# S7CAS-PLEIADES-CARTE-MERE_P01_FPGA-BANK1.net
KiCad netlist of a schematic drawn in Altium Designer
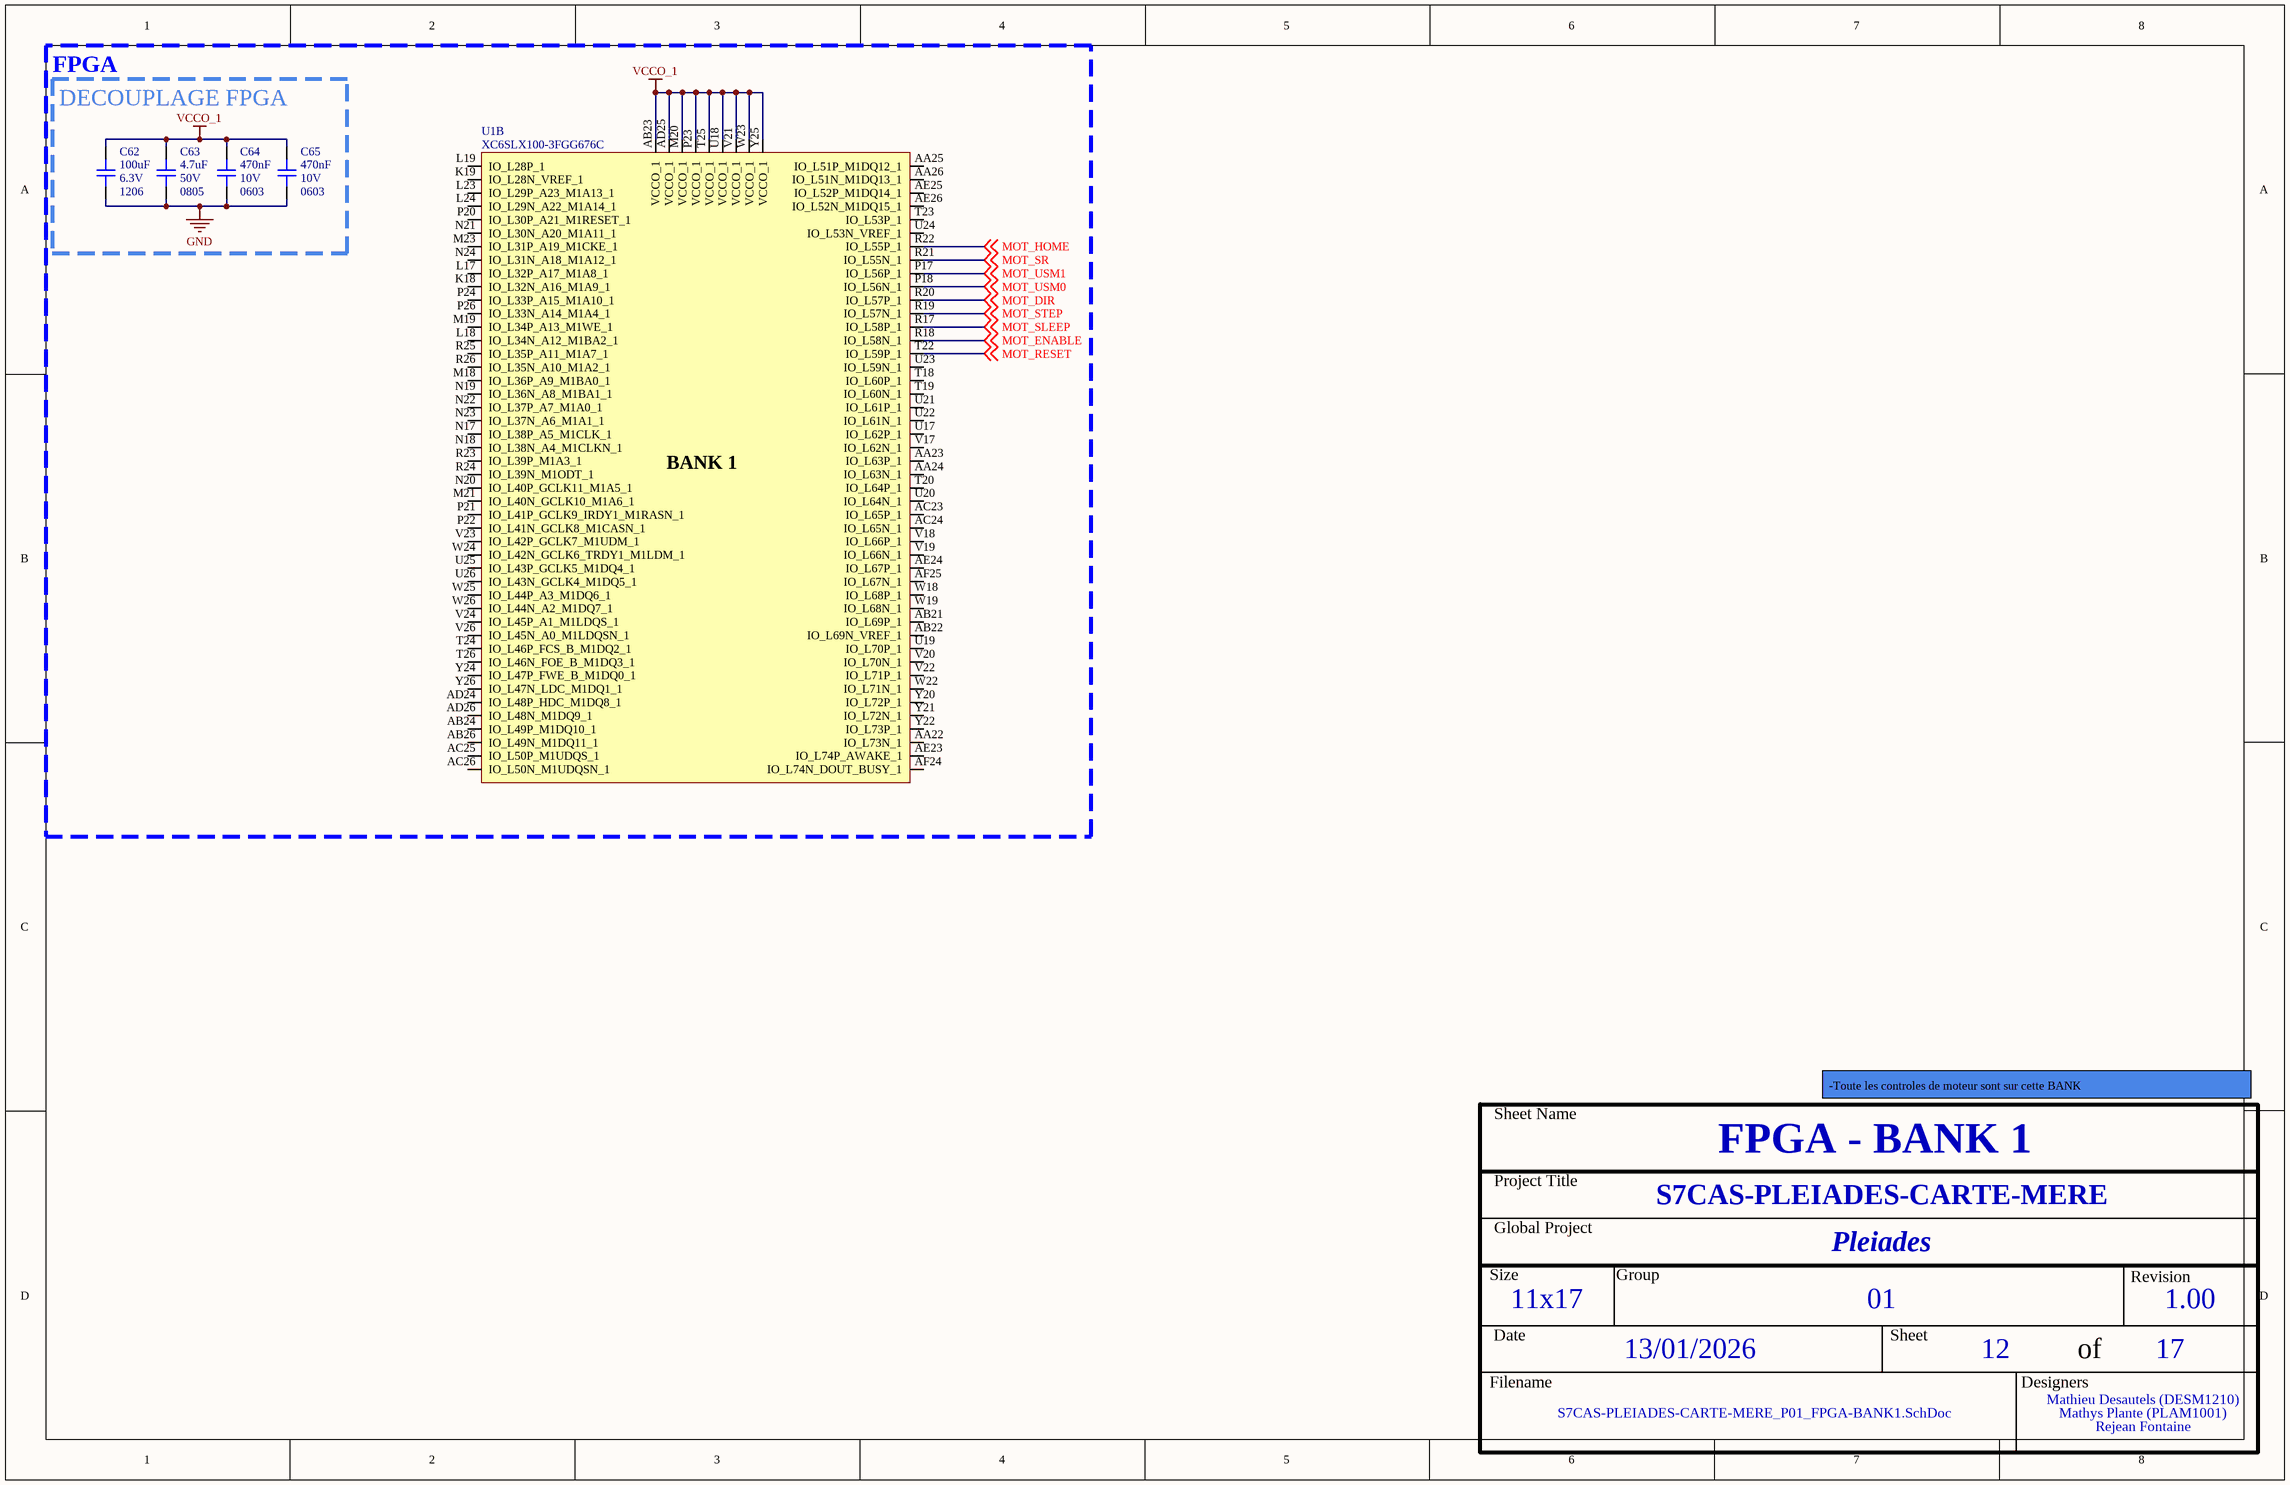
[diagram p0: S7CAS-PLEIADES-CARTE-MERE_P01_FPGA-BANK1.SchDoc]

(export (version "E")
  (design (tool "Eeschema 10.0.6"))
  (components
    (comp (ref "C62")
      (value "100uF")
      (footprint "CAP_1206")
      (description "100 µF ±20% 6.3V Ceramic Capacitor X6T 1206 (3216 Metric)")
      (fields
        (field (name "MFG") "Murata Electronics")
        (field (name "MFG PART NUMBER") "GRM31CD80J107MEA8K")
        (field (name "VOLTAGE") "6.3V")
        (field (name "PACKAGE") "1206")
        (field (name "CREATEDBY") "Jonathan Bouchard")
      )
      (libsource (lib "s7cas_lib2023") (part "CAP - 1206"))
    )
    (comp (ref "C63")
      (value "4.7uF")
      (footprint "CAP_0805")
      (description "4.7 µF ±10% 50V Ceramic Capacitor X5R 0805 (2012 Metric)")
      (fields
        (field (name "MFG") "Murata Electronics")
        (field (name "MFG PART NUMBER") "GRT21BR61H475KE13L")
        (field (name "VOLTAGE") "50V")
        (field (name "PACKAGE") "0805")
        (field (name "CREATEDBY") "Jonathan Bouchard")
      )
      (libsource (lib "s7cas_lib2023") (part "CAP - 0805"))
    )
    (comp (ref "C64")
      (value "470nF")
      (footprint "CAP_0603")
      (description "CAP - 0603")
      (fields
        (field (name "MFG PART NUMBER") "C0603X474K8RAC")
        (field (name "VOLTAGE") "10V")
        (field (name "PACKAGE") "0603")
        (field (name "CREATEDBY") "Jonathan Bouchard")
      )
      (libsource (lib "s7cas_lib2023") (part "CAP - 0603"))
    )
    (comp (ref "C65")
      (value "470nF")
      (footprint "CAP_0603")
      (description "CAP - 0603")
      (fields
        (field (name "MFG PART NUMBER") "C0603X474K8RAC")
        (field (name "VOLTAGE") "10V")
        (field (name "PACKAGE") "0603")
        (field (name "CREATEDBY") "Jonathan Bouchard")
      )
      (libsource (lib "s7cas_lib2023") (part "CAP - 0603"))
    )
    (comp (ref "U1")
      (value "XC6SLX100-3FGG676C")
      (footprint "FPGA_XILINX_FGG676")
      (description "FPGA - XILINX SPARTAN 6 480 I/O - BGA-676")
      (fields
        (field (name "VOLTAGE") "1.14 V ~ 1.26 V")
        (field (name "MFG") "Xilinx")
        (field (name "CREATEDBY") "Jonathan Bouchard")
      )
      (libsource (lib "s7cas_lib2023") (part "FPGA_XC6SLX100-3FGG676C"))
    )
  )
  (nets
    (net (code "1") (name "GND") (class "Default")
      (node (ref "C62") (pin "1") (pinfunction "1_1") (pintype "passive"))
      (node (ref "C63") (pin "1") (pinfunction "1_1") (pintype "passive"))
      (node (ref "C64") (pin "1") (pinfunction "1_1") (pintype "passive"))
      (node (ref "C65") (pin "1") (pinfunction "1_1") (pintype "passive"))
    )
    (net (code "2") (name "MOT_DIR") (class "Default")
      (node (ref "U1") (pin "R20") (pinfunction "IO_L57P_1_R20") (pintype "passive"))
    )
    (net (code "3") (name "MOT_ENABLE") (class "Default")
      (node (ref "U1") (pin "R18") (pinfunction "IO_L58N_1_R18") (pintype "passive"))
    )
    (net (code "4") (name "MOT_HOME") (class "Default")
      (node (ref "U1") (pin "R22") (pinfunction "IO_L55P_1_R22") (pintype "passive"))
    )
    (net (code "5") (name "MOT_RESET") (class "Default")
      (node (ref "U1") (pin "T22") (pinfunction "IO_L59P_1_T22") (pintype "passive"))
    )
    (net (code "6") (name "MOT_SLEEP") (class "Default")
      (node (ref "U1") (pin "R17") (pinfunction "IO_L58P_1_R17") (pintype "passive"))
    )
    (net (code "7") (name "MOT_SR") (class "Default")
      (node (ref "U1") (pin "R21") (pinfunction "IO_L55N_1_R21") (pintype "passive"))
    )
    (net (code "8") (name "MOT_STEP") (class "Default")
      (node (ref "U1") (pin "R19") (pinfunction "IO_L57N_1_R19") (pintype "passive"))
    )
    (net (code "9") (name "MOT_USM0") (class "Default")
      (node (ref "U1") (pin "P18") (pinfunction "IO_L56N_1_P18") (pintype "passive"))
    )
    (net (code "10") (name "MOT_USM1") (class "Default")
      (node (ref "U1") (pin "P17") (pinfunction "IO_L56P_1_P17") (pintype "passive"))
    )
    (net (code "11") (name "VCCO_1") (class "Default")
      (node (ref "C62") (pin "2") (pinfunction "2_2") (pintype "passive"))
      (node (ref "C63") (pin "2") (pinfunction "2_2") (pintype "passive"))
      (node (ref "C64") (pin "2") (pinfunction "2_2") (pintype "passive"))
      (node (ref "C65") (pin "2") (pinfunction "2_2") (pintype "passive"))
      (node (ref "U1") (pin "AB23") (pinfunction "VCCO_1_AB23") (pintype "passive"))
      (node (ref "U1") (pin "AD25") (pinfunction "VCCO_1_AD25") (pintype "passive"))
      (node (ref "U1") (pin "M20") (pinfunction "VCCO_1_M20") (pintype "passive"))
      (node (ref "U1") (pin "P23") (pinfunction "VCCO_1_P23") (pintype "passive"))
      (node (ref "U1") (pin "T25") (pinfunction "VCCO_1_T25") (pintype "passive"))
      (node (ref "U1") (pin "U18") (pinfunction "VCCO_1_U18") (pintype "passive"))
      (node (ref "U1") (pin "V21") (pinfunction "VCCO_1_V21") (pintype "passive"))
      (node (ref "U1") (pin "W23") (pinfunction "VCCO_1_W23") (pintype "passive"))
      (node (ref "U1") (pin "Y25") (pinfunction "VCCO_1_Y25") (pintype "passive"))
    )
    (net (code "12") (name "unconnected-(U1B-IO_L28N_VREF_1-PadK19)") (class "Default")
      (node (ref "U1") (pin "K19") (pinfunction "IO_L28N_VREF_1_K19") (pintype "passive"))
    )
    (net (code "13") (name "unconnected-(U1B-IO_L28P_1-PadL19)") (class "Default")
      (node (ref "U1") (pin "L19") (pinfunction "IO_L28P_1_L19") (pintype "passive"))
    )
    (net (code "14") (name "unconnected-(U1B-IO_L29N_A22_M1A14_1-PadL24)") (class "Default")
      (node (ref "U1") (pin "L24") (pinfunction "IO_L29N_A22_M1A14_1_L24") (pintype "passive"))
    )
    (net (code "15") (name "unconnected-(U1B-IO_L29P_A23_M1A13_1-PadL23)") (class "Default")
      (node (ref "U1") (pin "L23") (pinfunction "IO_L29P_A23_M1A13_1_L23") (pintype "passive"))
    )
    (net (code "16") (name "unconnected-(U1B-IO_L30N_A20_M1A11_1-PadN21)") (class "Default")
      (node (ref "U1") (pin "N21") (pinfunction "IO_L30N_A20_M1A11_1_N21") (pintype "passive"))
    )
    (net (code "17") (name "unconnected-(U1B-IO_L30P_A21_M1RESET_1-PadP20)") (class "Default")
      (node (ref "U1") (pin "P20") (pinfunction "IO_L30P_A21_M1RESET_1_P20") (pintype "passive"))
    )
    (net (code "18") (name "unconnected-(U1B-IO_L31N_A18_M1A12_1-PadN24)") (class "Default")
      (node (ref "U1") (pin "N24") (pinfunction "IO_L31N_A18_M1A12_1_N24") (pintype "passive"))
    )
    (net (code "19") (name "unconnected-(U1B-IO_L31P_A19_M1CKE_1-PadM23)") (class "Default")
      (node (ref "U1") (pin "M23") (pinfunction "IO_L31P_A19_M1CKE_1_M23") (pintype "passive"))
    )
    (net (code "20") (name "unconnected-(U1B-IO_L32N_A16_M1A9_1-PadK18)") (class "Default")
      (node (ref "U1") (pin "K18") (pinfunction "IO_L32N_A16_M1A9_1_K18") (pintype "passive"))
    )
    (net (code "21") (name "unconnected-(U1B-IO_L32P_A17_M1A8_1-PadL17)") (class "Default")
      (node (ref "U1") (pin "L17") (pinfunction "IO_L32P_A17_M1A8_1_L17") (pintype "passive"))
    )
    (net (code "22") (name "unconnected-(U1B-IO_L33N_A14_M1A4_1-PadP26)") (class "Default")
      (node (ref "U1") (pin "P26") (pinfunction "IO_L33N_A14_M1A4_1_P26") (pintype "passive"))
    )
    (net (code "23") (name "unconnected-(U1B-IO_L33P_A15_M1A10_1-PadP24)") (class "Default")
      (node (ref "U1") (pin "P24") (pinfunction "IO_L33P_A15_M1A10_1_P24") (pintype "passive"))
    )
    (net (code "24") (name "unconnected-(U1B-IO_L34N_A12_M1BA2_1-PadL18)") (class "Default")
      (node (ref "U1") (pin "L18") (pinfunction "IO_L34N_A12_M1BA2_1_L18") (pintype "passive"))
    )
    (net (code "25") (name "unconnected-(U1B-IO_L34P_A13_M1WE_1-PadM19)") (class "Default")
      (node (ref "U1") (pin "M19") (pinfunction "IO_L34P_A13_M1WE_1_M19") (pintype "passive"))
    )
    (net (code "26") (name "unconnected-(U1B-IO_L35N_A10_M1A2_1-PadR26)") (class "Default")
      (node (ref "U1") (pin "R26") (pinfunction "IO_L35N_A10_M1A2_1_R26") (pintype "passive"))
    )
    (net (code "27") (name "unconnected-(U1B-IO_L35P_A11_M1A7_1-PadR25)") (class "Default")
      (node (ref "U1") (pin "R25") (pinfunction "IO_L35P_A11_M1A7_1_R25") (pintype "passive"))
    )
    (net (code "28") (name "unconnected-(U1B-IO_L36N_A8_M1BA1_1-PadN19)") (class "Default")
      (node (ref "U1") (pin "N19") (pinfunction "IO_L36N_A8_M1BA1_1_N19") (pintype "passive"))
    )
    (net (code "29") (name "unconnected-(U1B-IO_L36P_A9_M1BA0_1-PadM18)") (class "Default")
      (node (ref "U1") (pin "M18") (pinfunction "IO_L36P_A9_M1BA0_1_M18") (pintype "passive"))
    )
    (net (code "30") (name "unconnected-(U1B-IO_L37N_A6_M1A1_1-PadN23)") (class "Default")
      (node (ref "U1") (pin "N23") (pinfunction "IO_L37N_A6_M1A1_1_N23") (pintype "passive"))
    )
    (net (code "31") (name "unconnected-(U1B-IO_L37P_A7_M1A0_1-PadN22)") (class "Default")
      (node (ref "U1") (pin "N22") (pinfunction "IO_L37P_A7_M1A0_1_N22") (pintype "passive"))
    )
    (net (code "32") (name "unconnected-(U1B-IO_L38N_A4_M1CLKN_1-PadN18)") (class "Default")
      (node (ref "U1") (pin "N18") (pinfunction "IO_L38N_A4_M1CLKN_1_N18") (pintype "passive"))
    )
    (net (code "33") (name "unconnected-(U1B-IO_L38P_A5_M1CLK_1-PadN17)") (class "Default")
      (node (ref "U1") (pin "N17") (pinfunction "IO_L38P_A5_M1CLK_1_N17") (pintype "passive"))
    )
    (net (code "34") (name "unconnected-(U1B-IO_L39N_M1ODT_1-PadR24)") (class "Default")
      (node (ref "U1") (pin "R24") (pinfunction "IO_L39N_M1ODT_1_R24") (pintype "passive"))
    )
    (net (code "35") (name "unconnected-(U1B-IO_L39P_M1A3_1-PadR23)") (class "Default")
      (node (ref "U1") (pin "R23") (pinfunction "IO_L39P_M1A3_1_R23") (pintype "passive"))
    )
    (net (code "36") (name "unconnected-(U1B-IO_L40N_GCLK10_M1A6_1-PadM21)") (class "Default")
      (node (ref "U1") (pin "M21") (pinfunction "IO_L40N_GCLK10_M1A6_1_M21") (pintype "passive"))
    )
    (net (code "37") (name "unconnected-(U1B-IO_L40P_GCLK11_M1A5_1-PadN20)") (class "Default")
      (node (ref "U1") (pin "N20") (pinfunction "IO_L40P_GCLK11_M1A5_1_N20") (pintype "passive"))
    )
    (net (code "38") (name "unconnected-(U1B-IO_L41N_GCLK8_M1CASN_1-PadP22)") (class "Default")
      (node (ref "U1") (pin "P22") (pinfunction "IO_L41N_GCLK8_M1CASN_1_P22") (pintype "passive"))
    )
    (net (code "39") (name "unconnected-(U1B-IO_L41P_GCLK9_IRDY1_M1RASN_1-PadP21)") (class "Default")
      (node (ref "U1") (pin "P21") (pinfunction "IO_L41P_GCLK9_IRDY1_M1RASN_1_P21") (pintype "passive"))
    )
    (net (code "40") (name "unconnected-(U1B-IO_L42N_GCLK6_TRDY1_M1LDM_1-PadW24)") (class "Default")
      (node (ref "U1") (pin "W24") (pinfunction "IO_L42N_GCLK6_TRDY1_M1LDM_1_W24") (pintype "passive"))
    )
    (net (code "41") (name "unconnected-(U1B-IO_L42P_GCLK7_M1UDM_1-PadV23)") (class "Default")
      (node (ref "U1") (pin "V23") (pinfunction "IO_L42P_GCLK7_M1UDM_1_V23") (pintype "passive"))
    )
    (net (code "42") (name "unconnected-(U1B-IO_L43N_GCLK4_M1DQ5_1-PadU26)") (class "Default")
      (node (ref "U1") (pin "U26") (pinfunction "IO_L43N_GCLK4_M1DQ5_1_U26") (pintype "passive"))
    )
    (net (code "43") (name "unconnected-(U1B-IO_L43P_GCLK5_M1DQ4_1-PadU25)") (class "Default")
      (node (ref "U1") (pin "U25") (pinfunction "IO_L43P_GCLK5_M1DQ4_1_U25") (pintype "passive"))
    )
    (net (code "44") (name "unconnected-(U1B-IO_L44N_A2_M1DQ7_1-PadW26)") (class "Default")
      (node (ref "U1") (pin "W26") (pinfunction "IO_L44N_A2_M1DQ7_1_W26") (pintype "passive"))
    )
    (net (code "45") (name "unconnected-(U1B-IO_L44P_A3_M1DQ6_1-PadW25)") (class "Default")
      (node (ref "U1") (pin "W25") (pinfunction "IO_L44P_A3_M1DQ6_1_W25") (pintype "passive"))
    )
    (net (code "46") (name "unconnected-(U1B-IO_L45N_A0_M1LDQSN_1-PadV26)") (class "Default")
      (node (ref "U1") (pin "V26") (pinfunction "IO_L45N_A0_M1LDQSN_1_V26") (pintype "passive"))
    )
    (net (code "47") (name "unconnected-(U1B-IO_L45P_A1_M1LDQS_1-PadV24)") (class "Default")
      (node (ref "U1") (pin "V24") (pinfunction "IO_L45P_A1_M1LDQS_1_V24") (pintype "passive"))
    )
    (net (code "48") (name "unconnected-(U1B-IO_L46N_FOE_B_M1DQ3_1-PadT26)") (class "Default")
      (node (ref "U1") (pin "T26") (pinfunction "IO_L46N_FOE_B_M1DQ3_1_T26") (pintype "passive"))
    )
    (net (code "49") (name "unconnected-(U1B-IO_L46P_FCS_B_M1DQ2_1-PadT24)") (class "Default")
      (node (ref "U1") (pin "T24") (pinfunction "IO_L46P_FCS_B_M1DQ2_1_T24") (pintype "passive"))
    )
    (net (code "50") (name "unconnected-(U1B-IO_L47N_LDC_M1DQ1_1-PadY26)") (class "Default")
      (node (ref "U1") (pin "Y26") (pinfunction "IO_L47N_LDC_M1DQ1_1_Y26") (pintype "passive"))
    )
    (net (code "51") (name "unconnected-(U1B-IO_L47P_FWE_B_M1DQ0_1-PadY24)") (class "Default")
      (node (ref "U1") (pin "Y24") (pinfunction "IO_L47P_FWE_B_M1DQ0_1_Y24") (pintype "passive"))
    )
    (net (code "52") (name "unconnected-(U1B-IO_L48N_M1DQ9_1-PadAD26)") (class "Default")
      (node (ref "U1") (pin "AD26") (pinfunction "IO_L48N_M1DQ9_1_AD26") (pintype "passive"))
    )
    (net (code "53") (name "unconnected-(U1B-IO_L48P_HDC_M1DQ8_1-PadAD24)") (class "Default")
      (node (ref "U1") (pin "AD24") (pinfunction "IO_L48P_HDC_M1DQ8_1_AD24") (pintype "passive"))
    )
    (net (code "54") (name "unconnected-(U1B-IO_L49N_M1DQ11_1-PadAB26)") (class "Default")
      (node (ref "U1") (pin "AB26") (pinfunction "IO_L49N_M1DQ11_1_AB26") (pintype "passive"))
    )
    (net (code "55") (name "unconnected-(U1B-IO_L49P_M1DQ10_1-PadAB24)") (class "Default")
      (node (ref "U1") (pin "AB24") (pinfunction "IO_L49P_M1DQ10_1_AB24") (pintype "passive"))
    )
    (net (code "56") (name "unconnected-(U1B-IO_L50N_M1UDQSN_1-PadAC26)") (class "Default")
      (node (ref "U1") (pin "AC26") (pinfunction "IO_L50N_M1UDQSN_1_AC26") (pintype "passive"))
    )
    (net (code "57") (name "unconnected-(U1B-IO_L50P_M1UDQS_1-PadAC25)") (class "Default")
      (node (ref "U1") (pin "AC25") (pinfunction "IO_L50P_M1UDQS_1_AC25") (pintype "passive"))
    )
    (net (code "58") (name "unconnected-(U1B-IO_L51N_M1DQ13_1-PadAA26)") (class "Default")
      (node (ref "U1") (pin "AA26") (pinfunction "IO_L51N_M1DQ13_1_AA26") (pintype "passive"))
    )
    (net (code "59") (name "unconnected-(U1B-IO_L51P_M1DQ12_1-PadAA25)") (class "Default")
      (node (ref "U1") (pin "AA25") (pinfunction "IO_L51P_M1DQ12_1_AA25") (pintype "passive"))
    )
    (net (code "60") (name "unconnected-(U1B-IO_L52N_M1DQ15_1-PadAE26)") (class "Default")
      (node (ref "U1") (pin "AE26") (pinfunction "IO_L52N_M1DQ15_1_AE26") (pintype "passive"))
    )
    (net (code "61") (name "unconnected-(U1B-IO_L52P_M1DQ14_1-PadAE25)") (class "Default")
      (node (ref "U1") (pin "AE25") (pinfunction "IO_L52P_M1DQ14_1_AE25") (pintype "passive"))
    )
    (net (code "62") (name "unconnected-(U1B-IO_L53N_VREF_1-PadU24)") (class "Default")
      (node (ref "U1") (pin "U24") (pinfunction "IO_L53N_VREF_1_U24") (pintype "passive"))
    )
    (net (code "63") (name "unconnected-(U1B-IO_L53P_1-PadT23)") (class "Default")
      (node (ref "U1") (pin "T23") (pinfunction "IO_L53P_1_T23") (pintype "passive"))
    )
    (net (code "64") (name "unconnected-(U1B-IO_L59N_1-PadU23)") (class "Default")
      (node (ref "U1") (pin "U23") (pinfunction "IO_L59N_1_U23") (pintype "passive"))
    )
    (net (code "65") (name "unconnected-(U1B-IO_L60N_1-PadT19)") (class "Default")
      (node (ref "U1") (pin "T19") (pinfunction "IO_L60N_1_T19") (pintype "passive"))
    )
    (net (code "66") (name "unconnected-(U1B-IO_L60P_1-PadT18)") (class "Default")
      (node (ref "U1") (pin "T18") (pinfunction "IO_L60P_1_T18") (pintype "passive"))
    )
    (net (code "67") (name "unconnected-(U1B-IO_L61N_1-PadU22)") (class "Default")
      (node (ref "U1") (pin "U22") (pinfunction "IO_L61N_1_U22") (pintype "passive"))
    )
    (net (code "68") (name "unconnected-(U1B-IO_L61P_1-PadU21)") (class "Default")
      (node (ref "U1") (pin "U21") (pinfunction "IO_L61P_1_U21") (pintype "passive"))
    )
    (net (code "69") (name "unconnected-(U1B-IO_L62N_1-PadV17)") (class "Default")
      (node (ref "U1") (pin "V17") (pinfunction "IO_L62N_1_V17") (pintype "passive"))
    )
    (net (code "70") (name "unconnected-(U1B-IO_L62P_1-PadU17)") (class "Default")
      (node (ref "U1") (pin "U17") (pinfunction "IO_L62P_1_U17") (pintype "passive"))
    )
    (net (code "71") (name "unconnected-(U1B-IO_L63N_1-PadAA24)") (class "Default")
      (node (ref "U1") (pin "AA24") (pinfunction "IO_L63N_1_AA24") (pintype "passive"))
    )
    (net (code "72") (name "unconnected-(U1B-IO_L63P_1-PadAA23)") (class "Default")
      (node (ref "U1") (pin "AA23") (pinfunction "IO_L63P_1_AA23") (pintype "passive"))
    )
    (net (code "73") (name "unconnected-(U1B-IO_L64N_1-PadU20)") (class "Default")
      (node (ref "U1") (pin "U20") (pinfunction "IO_L64N_1_U20") (pintype "passive"))
    )
    (net (code "74") (name "unconnected-(U1B-IO_L64P_1-PadT20)") (class "Default")
      (node (ref "U1") (pin "T20") (pinfunction "IO_L64P_1_T20") (pintype "passive"))
    )
    (net (code "75") (name "unconnected-(U1B-IO_L65N_1-PadAC24)") (class "Default")
      (node (ref "U1") (pin "AC24") (pinfunction "IO_L65N_1_AC24") (pintype "passive"))
    )
    (net (code "76") (name "unconnected-(U1B-IO_L65P_1-PadAC23)") (class "Default")
      (node (ref "U1") (pin "AC23") (pinfunction "IO_L65P_1_AC23") (pintype "passive"))
    )
    (net (code "77") (name "unconnected-(U1B-IO_L66N_1-PadV19)") (class "Default")
      (node (ref "U1") (pin "V19") (pinfunction "IO_L66N_1_V19") (pintype "passive"))
    )
    (net (code "78") (name "unconnected-(U1B-IO_L66P_1-PadV18)") (class "Default")
      (node (ref "U1") (pin "V18") (pinfunction "IO_L66P_1_V18") (pintype "passive"))
    )
    (net (code "79") (name "unconnected-(U1B-IO_L67N_1-PadAF25)") (class "Default")
      (node (ref "U1") (pin "AF25") (pinfunction "IO_L67N_1_AF25") (pintype "passive"))
    )
    (net (code "80") (name "unconnected-(U1B-IO_L67P_1-PadAE24)") (class "Default")
      (node (ref "U1") (pin "AE24") (pinfunction "IO_L67P_1_AE24") (pintype "passive"))
    )
    (net (code "81") (name "unconnected-(U1B-IO_L68N_1-PadW19)") (class "Default")
      (node (ref "U1") (pin "W19") (pinfunction "IO_L68N_1_W19") (pintype "passive"))
    )
    (net (code "82") (name "unconnected-(U1B-IO_L68P_1-PadW18)") (class "Default")
      (node (ref "U1") (pin "W18") (pinfunction "IO_L68P_1_W18") (pintype "passive"))
    )
    (net (code "83") (name "unconnected-(U1B-IO_L69N_VREF_1-PadAB22)") (class "Default")
      (node (ref "U1") (pin "AB22") (pinfunction "IO_L69N_VREF_1_AB22") (pintype "passive"))
    )
    (net (code "84") (name "unconnected-(U1B-IO_L69P_1-PadAB21)") (class "Default")
      (node (ref "U1") (pin "AB21") (pinfunction "IO_L69P_1_AB21") (pintype "passive"))
    )
    (net (code "85") (name "unconnected-(U1B-IO_L70N_1-PadV20)") (class "Default")
      (node (ref "U1") (pin "V20") (pinfunction "IO_L70N_1_V20") (pintype "passive"))
    )
    (net (code "86") (name "unconnected-(U1B-IO_L70P_1-PadU19)") (class "Default")
      (node (ref "U1") (pin "U19") (pinfunction "IO_L70P_1_U19") (pintype "passive"))
    )
    (net (code "87") (name "unconnected-(U1B-IO_L71N_1-PadW22)") (class "Default")
      (node (ref "U1") (pin "W22") (pinfunction "IO_L71N_1_W22") (pintype "passive"))
    )
    (net (code "88") (name "unconnected-(U1B-IO_L71P_1-PadV22)") (class "Default")
      (node (ref "U1") (pin "V22") (pinfunction "IO_L71P_1_V22") (pintype "passive"))
    )
    (net (code "89") (name "unconnected-(U1B-IO_L72N_1-PadY21)") (class "Default")
      (node (ref "U1") (pin "Y21") (pinfunction "IO_L72N_1_Y21") (pintype "passive"))
    )
    (net (code "90") (name "unconnected-(U1B-IO_L72P_1-PadY20)") (class "Default")
      (node (ref "U1") (pin "Y20") (pinfunction "IO_L72P_1_Y20") (pintype "passive"))
    )
    (net (code "91") (name "unconnected-(U1B-IO_L73N_1-PadAA22)") (class "Default")
      (node (ref "U1") (pin "AA22") (pinfunction "IO_L73N_1_AA22") (pintype "passive"))
    )
    (net (code "92") (name "unconnected-(U1B-IO_L73P_1-PadY22)") (class "Default")
      (node (ref "U1") (pin "Y22") (pinfunction "IO_L73P_1_Y22") (pintype "passive"))
    )
    (net (code "93") (name "unconnected-(U1B-IO_L74N_DOUT_BUSY_1-PadAF24)") (class "Default")
      (node (ref "U1") (pin "AF24") (pinfunction "IO_L74N_DOUT_BUSY_1_AF24") (pintype "passive"))
    )
    (net (code "94") (name "unconnected-(U1B-IO_L74P_AWAKE_1-PadAE23)") (class "Default")
      (node (ref "U1") (pin "AE23") (pinfunction "IO_L74P_AWAKE_1_AE23") (pintype "passive"))
    )
  )
)
